# SCH_SENSORS_IRC_2024-07-05.net
KiCad netlist of a schematic drawn in EasyEDA
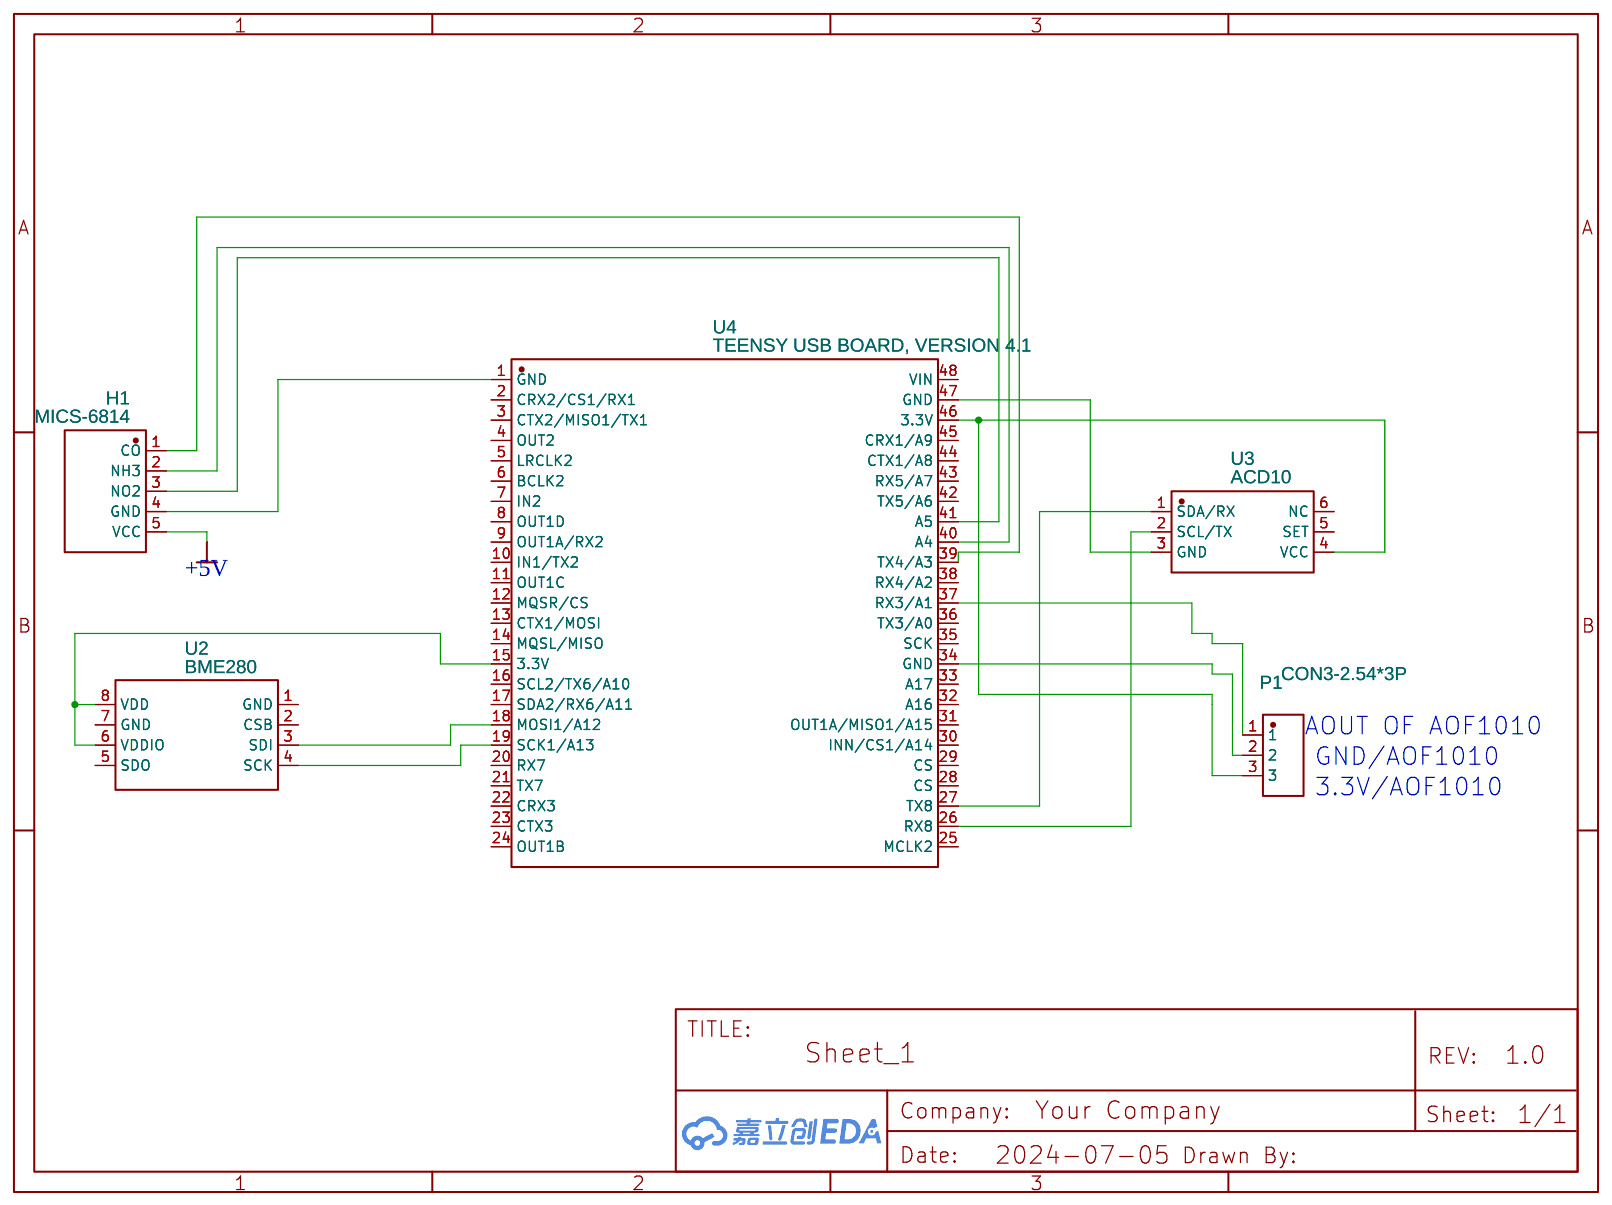
[diagram p0: schematic sheet]

(export (version "E")
  (design (tool "Eeschema 10.0.6"))
  (components
    (comp (ref "H1") (value "MICS-6814") (libsource (lib "") (part "MICS-6814")))
    (comp (ref "P1") (value "CON3-2.54*3P") (libsource (lib "") (part "CON3-2.54*3P")))
    (comp (ref "U2")
      (value "BME280")
      (fields (field (name "Manufacturer") "Bosch(博世)"))
      (libsource (lib "") (part "BME280"))
    )
    (comp (ref "U3")
      (value "ACD10")
      (fields (field (name "Manufacturer") "广州奥松"))
      (libsource (lib "") (part "ACD10"))
    )
    (comp (ref "U4")
      (value "TEENSY USB BOARD, VERSION 4.1")
      (fields (field (name "Manufacturer Part") "Teensy USB Board, Version 4.1"))
      (libsource (lib "") (part "TEENSY USB BOARD, VERSION 4.1"))
    )
  )
  (nets
    (net (code "1") (name "+5V") (class "Default")
      (node (ref "H1") (pin "5") (pinfunction "VCC_5") (pintype "unspecified"))
    )
    (net (code "2") (name "Net-(H1-CO)") (class "Default")
      (node (ref "H1") (pin "1") (pinfunction "CO_1") (pintype "unspecified"))
      (node (ref "U4") (pin "39") (pinfunction "TX4/A3_39") (pintype "unspecified"))
    )
    (net (code "3") (name "Net-(H1-GND)") (class "Default")
      (node (ref "H1") (pin "4") (pinfunction "GND_4") (pintype "unspecified"))
      (node (ref "U4") (pin "1") (pinfunction "GND_1") (pintype "unspecified"))
    )
    (net (code "4") (name "Net-(H1-NH3)") (class "Default")
      (node (ref "H1") (pin "2") (pinfunction "NH3_2") (pintype "unspecified"))
      (node (ref "U4") (pin "40") (pinfunction "A4_40") (pintype "unspecified"))
    )
    (net (code "5") (name "Net-(H1-NO2)") (class "Default")
      (node (ref "H1") (pin "3") (pinfunction "NO2_3") (pintype "unspecified"))
      (node (ref "U4") (pin "41") (pinfunction "A5_41") (pintype "unspecified"))
    )
    (net (code "6") (name "Net-(P1-Pad2)") (class "Default")
      (node (ref "P1") (pin "2") (pinfunction "2_2") (pintype "unspecified"))
      (node (ref "U4") (pin "34") (pinfunction "GND_34") (pintype "unspecified"))
    )
    (net (code "7") (name "Net-(U2-SCK)") (class "Default")
      (node (ref "U2") (pin "4") (pinfunction "SCK_4") (pintype "unspecified"))
      (node (ref "U4") (pin "19") (pinfunction "SCK1/A13_19") (pintype "unspecified"))
    )
    (net (code "8") (name "Net-(U2-SDI)") (class "Default")
      (node (ref "U2") (pin "3") (pinfunction "SDI_3") (pintype "unspecified"))
      (node (ref "U4") (pin "18") (pinfunction "MOSI1/A12_18") (pintype "unspecified"))
    )
    (net (code "9") (name "Net-(U2-VDD)") (class "Default")
      (node (ref "U2") (pin "6") (pinfunction "VDDIO_6") (pintype "unspecified"))
      (node (ref "U2") (pin "8") (pinfunction "VDD_8") (pintype "unspecified"))
      (node (ref "U4") (pin "15") (pinfunction "3.3V_15") (pintype "unspecified"))
    )
    (net (code "10") (name "Net-(U3-GND)") (class "Default")
      (node (ref "U3") (pin "3") (pinfunction "GND_3") (pintype "unspecified"))
      (node (ref "U4") (pin "47") (pinfunction "GND_47") (pintype "unspecified"))
    )
    (net (code "11") (name "Net-(U3-SCL{slash}TX)") (class "Default")
      (node (ref "U3") (pin "2") (pinfunction "SCL/TX_2") (pintype "unspecified"))
      (node (ref "U4") (pin "26") (pinfunction "RX8_26") (pintype "unspecified"))
    )
    (net (code "12") (name "Net-(U3-SDA{slash}RX)") (class "Default")
      (node (ref "U3") (pin "1") (pinfunction "SDA/RX_1") (pintype "unspecified"))
      (node (ref "U4") (pin "27") (pinfunction "TX8_27") (pintype "unspecified"))
    )
    (net (code "13") (name "Net-(U3-VCC)") (class "Default")
      (node (ref "P1") (pin "3") (pinfunction "3_3") (pintype "unspecified"))
      (node (ref "U3") (pin "4") (pinfunction "VCC_4") (pintype "unspecified"))
      (node (ref "U4") (pin "46") (pinfunction "3.3V_46") (pintype "unspecified"))
    )
    (net (code "14") (name "Net-(U4-RX3{slash}A1)") (class "Default")
      (node (ref "P1") (pin "1") (pinfunction "1_1") (pintype "unspecified"))
      (node (ref "U4") (pin "37") (pinfunction "RX3/A1_37") (pintype "unspecified"))
    )
    (net (code "15") (name "unconnected-(U2-CSB-Pad2)") (class "Default")
      (node (ref "U2") (pin "2") (pinfunction "CSB_2") (pintype "unspecified"))
    )
    (net (code "16") (name "unconnected-(U2-GND-Pad1)") (class "Default")
      (node (ref "U2") (pin "1") (pinfunction "GND_1") (pintype "unspecified"))
    )
    (net (code "17") (name "unconnected-(U2-GND-Pad7)") (class "Default")
      (node (ref "U2") (pin "7") (pinfunction "GND_7") (pintype "unspecified"))
    )
    (net (code "18") (name "unconnected-(U2-SDO-Pad5)") (class "Default")
      (node (ref "U2") (pin "5") (pinfunction "SDO_5") (pintype "unspecified"))
    )
    (net (code "19") (name "unconnected-(U3-NC-Pad6)") (class "Default")
      (node (ref "U3") (pin "6") (pinfunction "NC_6") (pintype "unspecified"))
    )
    (net (code "20") (name "unconnected-(U3-SET-Pad5)") (class "Default")
      (node (ref "U3") (pin "5") (pinfunction "SET_5") (pintype "unspecified"))
    )
    (net (code "21") (name "unconnected-(U4-A16-Pad32)") (class "Default")
      (node (ref "U4") (pin "32") (pinfunction "A16_32") (pintype "unspecified"))
    )
    (net (code "22") (name "unconnected-(U4-A17-Pad33)") (class "Default")
      (node (ref "U4") (pin "33") (pinfunction "A17_33") (pintype "unspecified"))
    )
    (net (code "23") (name "unconnected-(U4-BCLK2-Pad6)") (class "Default")
      (node (ref "U4") (pin "6") (pinfunction "BCLK2_6") (pintype "unspecified"))
    )
    (net (code "24") (name "unconnected-(U4-CRX1{slash}A9-Pad45)") (class "Default")
      (node (ref "U4") (pin "45") (pinfunction "CRX1/A9_45") (pintype "unspecified"))
    )
    (net (code "25") (name "unconnected-(U4-CRX2{slash}CS1{slash}RX1-Pad2)") (class "Default")
      (node (ref "U4") (pin "2") (pinfunction "CRX2/CS1/RX1_2") (pintype "unspecified"))
    )
    (net (code "26") (name "unconnected-(U4-CRX3-Pad22)") (class "Default")
      (node (ref "U4") (pin "22") (pinfunction "CRX3_22") (pintype "unspecified"))
    )
    (net (code "27") (name "unconnected-(U4-CS-Pad28)") (class "Default")
      (node (ref "U4") (pin "28") (pinfunction "CS_28") (pintype "unspecified"))
    )
    (net (code "28") (name "unconnected-(U4-CS-Pad29)") (class "Default")
      (node (ref "U4") (pin "29") (pinfunction "CS_29") (pintype "unspecified"))
    )
    (net (code "29") (name "unconnected-(U4-CTX1{slash}A8-Pad44)") (class "Default")
      (node (ref "U4") (pin "44") (pinfunction "CTX1/A8_44") (pintype "unspecified"))
    )
    (net (code "30") (name "unconnected-(U4-CTX1{slash}MOSI-Pad13)") (class "Default")
      (node (ref "U4") (pin "13") (pinfunction "CTX1/MOSI_13") (pintype "unspecified"))
    )
    (net (code "31") (name "unconnected-(U4-CTX2{slash}MISO1{slash}TX1-Pad3)") (class "Default")
      (node (ref "U4") (pin "3") (pinfunction "CTX2/MISO1/TX1_3") (pintype "unspecified"))
    )
    (net (code "32") (name "unconnected-(U4-CTX3-Pad23)") (class "Default")
      (node (ref "U4") (pin "23") (pinfunction "CTX3_23") (pintype "unspecified"))
    )
    (net (code "33") (name "unconnected-(U4-IN1{slash}TX2-Pad10)") (class "Default")
      (node (ref "U4") (pin "10") (pinfunction "IN1/TX2_10") (pintype "unspecified"))
    )
    (net (code "34") (name "unconnected-(U4-IN2-Pad7)") (class "Default")
      (node (ref "U4") (pin "7") (pinfunction "IN2_7") (pintype "unspecified"))
    )
    (net (code "35") (name "unconnected-(U4-INN{slash}CS1{slash}A14-Pad30)") (class "Default")
      (node (ref "U4") (pin "30") (pinfunction "INN/CS1/A14_30") (pintype "unspecified"))
    )
    (net (code "36") (name "unconnected-(U4-LRCLK2-Pad5)") (class "Default")
      (node (ref "U4") (pin "5") (pinfunction "LRCLK2_5") (pintype "unspecified"))
    )
    (net (code "37") (name "unconnected-(U4-MCLK2-Pad25)") (class "Default")
      (node (ref "U4") (pin "25") (pinfunction "MCLK2_25") (pintype "unspecified"))
    )
    (net (code "38") (name "unconnected-(U4-MQSL{slash}MISO-Pad14)") (class "Default")
      (node (ref "U4") (pin "14") (pinfunction "MQSL/MISO_14") (pintype "unspecified"))
    )
    (net (code "39") (name "unconnected-(U4-MQSR{slash}CS-Pad12)") (class "Default")
      (node (ref "U4") (pin "12") (pinfunction "MQSR/CS_12") (pintype "unspecified"))
    )
    (net (code "40") (name "unconnected-(U4-OUT1A{slash}MISO1{slash}A15-Pad31)") (class "Default")
      (node (ref "U4") (pin "31") (pinfunction "OUT1A/MISO1/A15_31") (pintype "unspecified"))
    )
    (net (code "41") (name "unconnected-(U4-OUT1A{slash}RX2-Pad9)") (class "Default")
      (node (ref "U4") (pin "9") (pinfunction "OUT1A/RX2_9") (pintype "unspecified"))
    )
    (net (code "42") (name "unconnected-(U4-OUT1B-Pad24)") (class "Default")
      (node (ref "U4") (pin "24") (pinfunction "OUT1B_24") (pintype "unspecified"))
    )
    (net (code "43") (name "unconnected-(U4-OUT1C-Pad11)") (class "Default")
      (node (ref "U4") (pin "11") (pinfunction "OUT1C_11") (pintype "unspecified"))
    )
    (net (code "44") (name "unconnected-(U4-OUT1D-Pad8)") (class "Default")
      (node (ref "U4") (pin "8") (pinfunction "OUT1D_8") (pintype "unspecified"))
    )
    (net (code "45") (name "unconnected-(U4-OUT2-Pad4)") (class "Default")
      (node (ref "U4") (pin "4") (pinfunction "OUT2_4") (pintype "unspecified"))
    )
    (net (code "46") (name "unconnected-(U4-RX4{slash}A2-Pad38)") (class "Default")
      (node (ref "U4") (pin "38") (pinfunction "RX4/A2_38") (pintype "unspecified"))
    )
    (net (code "47") (name "unconnected-(U4-RX5{slash}A7-Pad43)") (class "Default")
      (node (ref "U4") (pin "43") (pinfunction "RX5/A7_43") (pintype "unspecified"))
    )
    (net (code "48") (name "unconnected-(U4-RX7-Pad20)") (class "Default")
      (node (ref "U4") (pin "20") (pinfunction "RX7_20") (pintype "unspecified"))
    )
    (net (code "49") (name "unconnected-(U4-SCK-Pad35)") (class "Default")
      (node (ref "U4") (pin "35") (pinfunction "SCK_35") (pintype "unspecified"))
    )
    (net (code "50") (name "unconnected-(U4-SCL2{slash}TX6{slash}A10-Pad16)") (class "Default")
      (node (ref "U4") (pin "16") (pinfunction "SCL2/TX6/A10_16") (pintype "unspecified"))
    )
    (net (code "51") (name "unconnected-(U4-SDA2{slash}RX6{slash}A11-Pad17)") (class "Default")
      (node (ref "U4") (pin "17") (pinfunction "SDA2/RX6/A11_17") (pintype "unspecified"))
    )
    (net (code "52") (name "unconnected-(U4-TX3{slash}A0-Pad36)") (class "Default")
      (node (ref "U4") (pin "36") (pinfunction "TX3/A0_36") (pintype "unspecified"))
    )
    (net (code "53") (name "unconnected-(U4-TX5{slash}A6-Pad42)") (class "Default")
      (node (ref "U4") (pin "42") (pinfunction "TX5/A6_42") (pintype "unspecified"))
    )
    (net (code "54") (name "unconnected-(U4-TX7-Pad21)") (class "Default")
      (node (ref "U4") (pin "21") (pinfunction "TX7_21") (pintype "unspecified"))
    )
    (net (code "55") (name "unconnected-(U4-VIN-Pad48)") (class "Default")
      (node (ref "U4") (pin "48") (pinfunction "VIN_48") (pintype "unspecified"))
    )
  )
)
